# power.net
KiCad netlist of a schematic drawn in Altium Designer
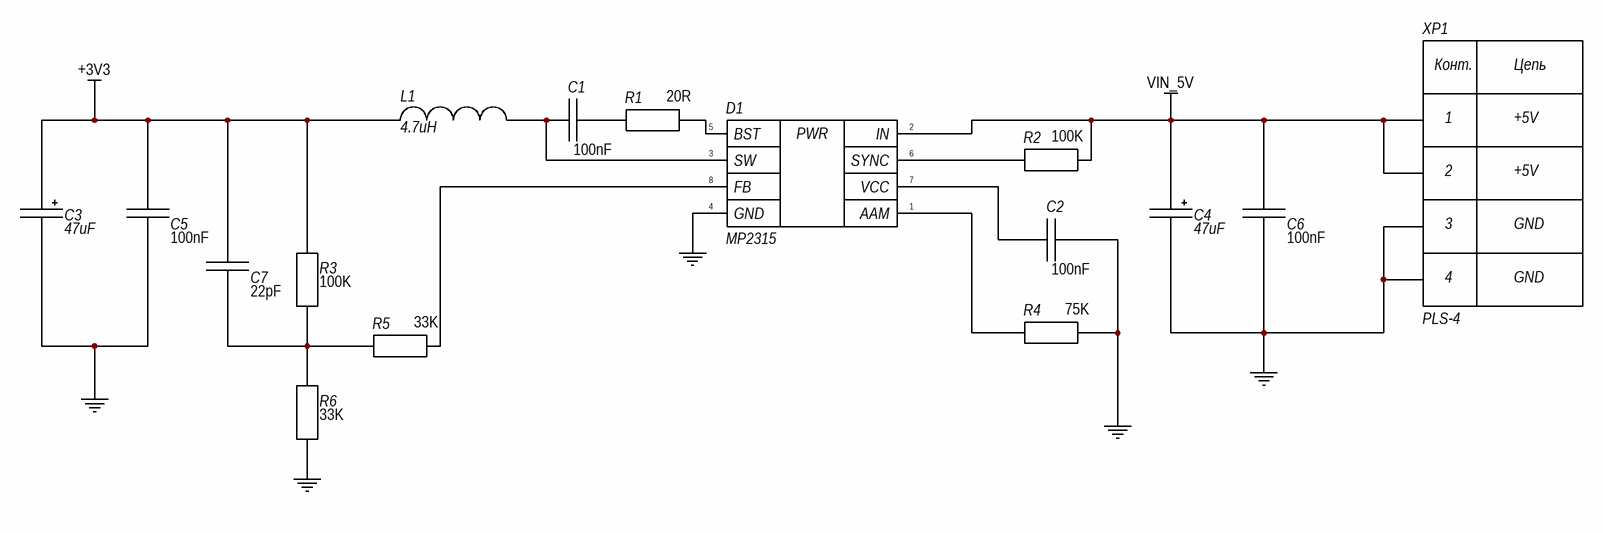
[diagram p0: power.SchDoc]

(export (version "E")
  (design (tool "Eeschema 10.0.6"))
  (components
    (comp (ref "C1")
      (value "100nF")
      (footprint "SMD 0805")
      (description "Конденсатор номиналом 1.5 nF")
      (libsource (lib "Capacitors") (part "100nF"))
    )
    (comp (ref "C2")
      (value "100nF")
      (footprint "SMD 0805")
      (description "Конденсатор номиналом 1.5 nF")
      (libsource (lib "Capacitors") (part "100nF"))
    )
    (comp (ref "C3")
      (value "47uF")
      (footprint "SMD47 ECAP")
      (description "Электролитический конденсатор номиналом 47uF")
      (libsource (lib "Capacitors") (part "47uF"))
    )
    (comp (ref "C4")
      (value "47uF")
      (footprint "SMD47 ECAP")
      (description "Электролитический конденсатор номиналом 47uF")
      (libsource (lib "Capacitors") (part "47uF"))
    )
    (comp (ref "C5")
      (value "100nF")
      (footprint "SMD 0805")
      (description "Конденсатор номиналом 1.5 nF")
      (libsource (lib "Capacitors") (part "100nF"))
    )
    (comp (ref "C6")
      (value "100nF")
      (footprint "SMD 0805")
      (description "Конденсатор номиналом 1.5 nF")
      (libsource (lib "Capacitors") (part "100nF"))
    )
    (comp (ref "C7")
      (value "22pF")
      (footprint "SMD 0805")
      (description "Конденсатор номиналом 22 pF")
      (libsource (lib "Capacitors") (part "22pF"))
    )
    (comp (ref "D1")
      (value "MP2315")
      (footprint "PWR_MP2315")
      (libsource (lib "Power Supplies") (part "MP2315"))
    )
    (comp (ref "L1")
      (value "4.7uH")
      (footprint "SP43-4R7M")
      (description "Катушка индуктивности 4.7 мкГн")
      (libsource (lib "Inductors & Transformers") (part "4.7u"))
    )
    (comp (ref "R1")
      (value "20R")
      (footprint "RESC0805")
      (description "Резистор номиналом 20 Ом")
      (libsource (lib "Resistors") (part "20R"))
    )
    (comp (ref "R2")
      (value "100K")
      (footprint "RESC0805")
      (description "Резистор номиналом 100 кОм")
      (libsource (lib "Resistors") (part "100K"))
    )
    (comp (ref "R3")
      (value "100K")
      (footprint "RESC0805")
      (description "Резистор номиналом 100 кОм")
      (libsource (lib "Resistors") (part "100K"))
    )
    (comp (ref "R4")
      (value "75K")
      (footprint "RESC0805")
      (description "Резистор номиналом 75 кОм")
      (libsource (lib "Resistors") (part "75K"))
    )
    (comp (ref "R5")
      (value "33K")
      (footprint "RESC0805")
      (description "Резистор номиналом 33 кОм")
      (libsource (lib "Resistors") (part "33K"))
    )
    (comp (ref "R6")
      (value "33K")
      (footprint "RESC0805")
      (description "Резистор номиналом 33 кОм")
      (libsource (lib "Resistors") (part "33K"))
    )
    (comp (ref "XP1")
      (value "PLS-4")
      (footprint "PLS-4")
      (description "SMT-разъём для связи платы ПП с периферийными устройствами")
      (libsource (lib "Connectors") (part "SMT_POWER"))
    )
  )
  (nets
    (net (code "1") (name "+3V3") (class "Default")
      (node (ref "C3") (pin "1") (pinfunction "1_1") (pintype "passive"))
      (node (ref "C5") (pin "2") (pinfunction "2_2") (pintype "passive"))
      (node (ref "C7") (pin "2") (pinfunction "2_2") (pintype "passive"))
      (node (ref "L1") (pin "1") (pinfunction "1_1") (pintype "passive"))
      (node (ref "R3") (pin "2") (pinfunction "2_2") (pintype "passive"))
    )
    (net (code "2") (name "GND") (class "Default")
      (node (ref "C2") (pin "1") (pinfunction "1_1") (pintype "passive"))
      (node (ref "C3") (pin "2") (pinfunction "2_2") (pintype "passive"))
      (node (ref "C4") (pin "2") (pinfunction "2_2") (pintype "passive"))
      (node (ref "C5") (pin "1") (pinfunction "1_1") (pintype "passive"))
      (node (ref "C6") (pin "2") (pinfunction "2_2") (pintype "passive"))
      (node (ref "D1") (pin "4") (pinfunction "GND_4") (pintype "passive"))
      (node (ref "R4") (pin "2") (pinfunction "2_2") (pintype "passive"))
      (node (ref "R6") (pin "1") (pinfunction "1_1") (pintype "passive"))
      (node (ref "XP1") (pin "3") (pinfunction "3_3") (pintype "passive"))
      (node (ref "XP1") (pin "4") (pinfunction "4_4") (pintype "passive"))
    )
    (net (code "3") (name "Net-(C1-Pad1)") (class "Default")
      (node (ref "C1") (pin "1") (pinfunction "1_1") (pintype "passive"))
      (node (ref "R1") (pin "1") (pinfunction "1_1") (pintype "passive"))
    )
    (net (code "4") (name "Net-(C7-Pad1)") (class "Default")
      (node (ref "C7") (pin "1") (pinfunction "1_1") (pintype "passive"))
      (node (ref "R3") (pin "1") (pinfunction "1_1") (pintype "passive"))
      (node (ref "R5") (pin "1") (pinfunction "1_1") (pintype "passive"))
      (node (ref "R6") (pin "2") (pinfunction "2_2") (pintype "passive"))
    )
    (net (code "5") (name "Net-(D1-AAM)") (class "Default")
      (node (ref "D1") (pin "1") (pinfunction "AAM_1") (pintype "passive"))
      (node (ref "R4") (pin "1") (pinfunction "1_1") (pintype "passive"))
    )
    (net (code "6") (name "Net-(D1-BST)") (class "Default")
      (node (ref "D1") (pin "5") (pinfunction "BST_5") (pintype "passive"))
      (node (ref "R1") (pin "2") (pinfunction "2_2") (pintype "passive"))
    )
    (net (code "7") (name "Net-(D1-FB)") (class "Default")
      (node (ref "D1") (pin "8") (pinfunction "FB_8") (pintype "passive"))
      (node (ref "R5") (pin "2") (pinfunction "2_2") (pintype "passive"))
    )
    (net (code "8") (name "Net-(D1-SW)") (class "Default")
      (node (ref "C1") (pin "2") (pinfunction "2_2") (pintype "passive"))
      (node (ref "D1") (pin "3") (pinfunction "SW_3") (pintype "passive"))
      (node (ref "L1") (pin "2") (pinfunction "2_2") (pintype "passive"))
    )
    (net (code "9") (name "Net-(D1-SYNC)") (class "Default")
      (node (ref "D1") (pin "6") (pinfunction "SYNC_6") (pintype "passive"))
      (node (ref "R2") (pin "1") (pinfunction "1_1") (pintype "passive"))
    )
    (net (code "10") (name "Net-(D1-VCC)") (class "Default")
      (node (ref "C2") (pin "2") (pinfunction "2_2") (pintype "passive"))
      (node (ref "D1") (pin "7") (pinfunction "VCC_7") (pintype "passive"))
    )
    (net (code "11") (name "VIN_5V") (class "Default")
      (node (ref "C4") (pin "1") (pinfunction "1_1") (pintype "passive"))
      (node (ref "C6") (pin "1") (pinfunction "1_1") (pintype "passive"))
      (node (ref "D1") (pin "2") (pinfunction "IN_2") (pintype "passive"))
      (node (ref "R2") (pin "2") (pinfunction "2_2") (pintype "passive"))
      (node (ref "XP1") (pin "1") (pinfunction "1_1") (pintype "passive"))
      (node (ref "XP1") (pin "2") (pinfunction "2_2") (pintype "passive"))
    )
  )
)
